# Array.net
KiCad netlist of a schematic drawn in Altium Designer
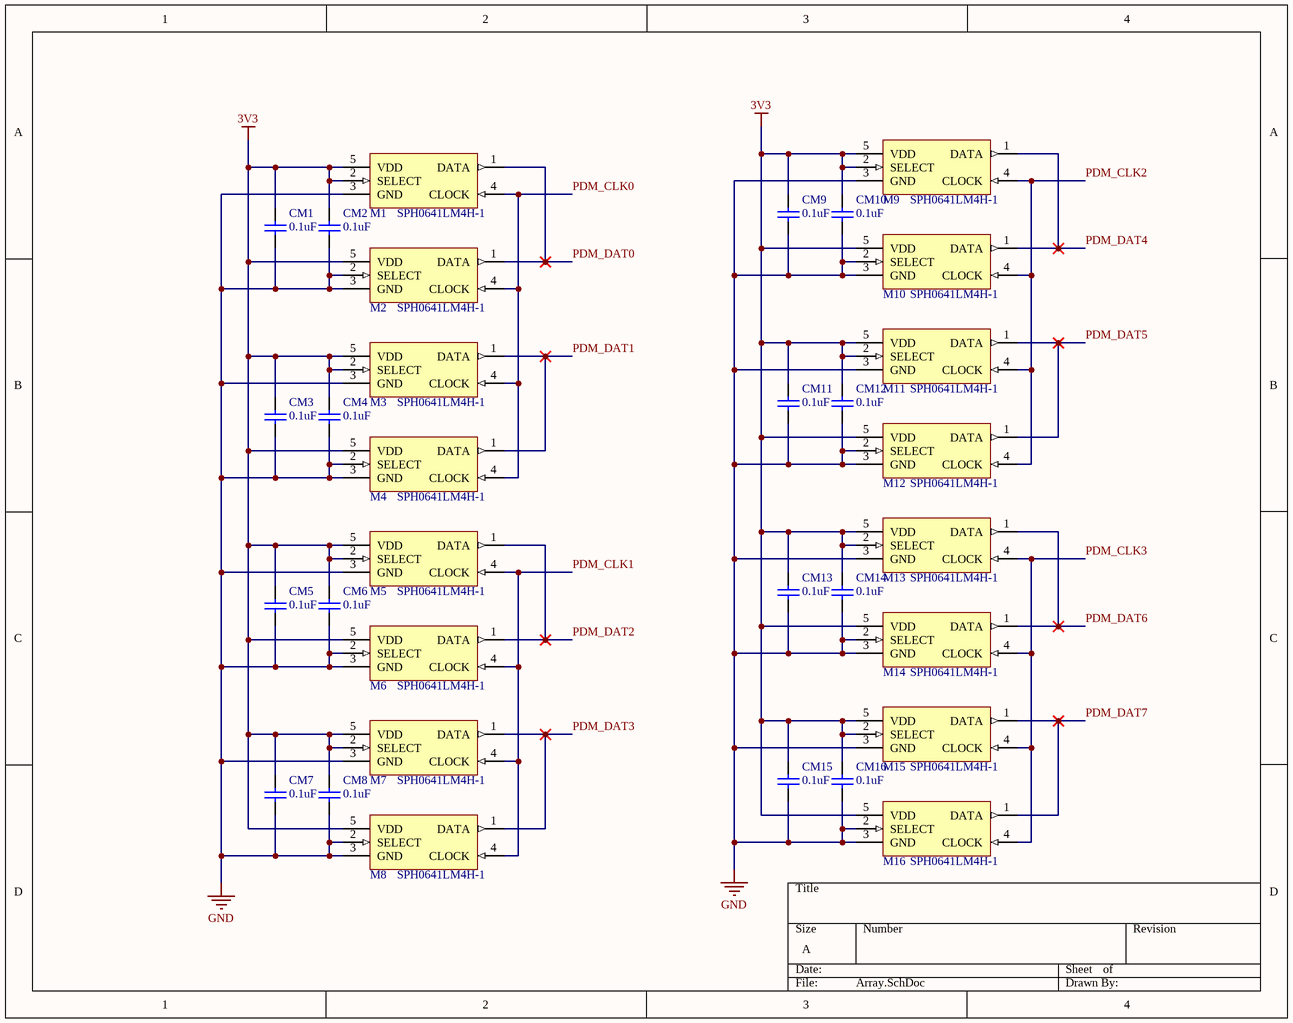
[diagram p0: Array.SchDoc]

(export (version "E")
  (design (tool "Eeschema 10.0.6"))
  (components
    (comp (ref "CM1")
      (value "0.1uF")
      (footprint "CHIP-0603")
      (description "Capacitor")
      (fields (field (name "PUBLISHER") "Altium Limited"))
      (libsource (lib "Miscellaneous Devices") (part "Cap"))
    )
    (comp (ref "CM2")
      (value "0.1uF")
      (footprint "CHIP-0603")
      (description "Capacitor")
      (fields (field (name "PUBLISHER") "Altium Limited"))
      (libsource (lib "Miscellaneous Devices") (part "Cap"))
    )
    (comp (ref "CM3")
      (value "0.1uF")
      (footprint "CHIP-0603")
      (description "Capacitor")
      (fields (field (name "PUBLISHER") "Altium Limited"))
      (libsource (lib "Miscellaneous Devices") (part "Cap"))
    )
    (comp (ref "CM4")
      (value "0.1uF")
      (footprint "CHIP-0603")
      (description "Capacitor")
      (fields (field (name "PUBLISHER") "Altium Limited"))
      (libsource (lib "Miscellaneous Devices") (part "Cap"))
    )
    (comp (ref "CM5")
      (value "0.1uF")
      (footprint "CHIP-0603")
      (description "Capacitor")
      (fields (field (name "PUBLISHER") "Altium Limited"))
      (libsource (lib "Miscellaneous Devices") (part "Cap"))
    )
    (comp (ref "CM6")
      (value "0.1uF")
      (footprint "CHIP-0603")
      (description "Capacitor")
      (fields (field (name "PUBLISHER") "Altium Limited"))
      (libsource (lib "Miscellaneous Devices") (part "Cap"))
    )
    (comp (ref "CM7")
      (value "0.1uF")
      (footprint "CHIP-0603")
      (description "Capacitor")
      (fields (field (name "PUBLISHER") "Altium Limited"))
      (libsource (lib "Miscellaneous Devices") (part "Cap"))
    )
    (comp (ref "CM8")
      (value "0.1uF")
      (footprint "CHIP-0603")
      (description "Capacitor")
      (fields (field (name "PUBLISHER") "Altium Limited"))
      (libsource (lib "Miscellaneous Devices") (part "Cap"))
    )
    (comp (ref "CM9")
      (value "0.1uF")
      (footprint "CHIP-0603")
      (description "Capacitor")
      (fields (field (name "PUBLISHER") "Altium Limited"))
      (libsource (lib "Miscellaneous Devices") (part "Cap"))
    )
    (comp (ref "CM10")
      (value "0.1uF")
      (footprint "CHIP-0603")
      (description "Capacitor")
      (fields (field (name "PUBLISHER") "Altium Limited"))
      (libsource (lib "Miscellaneous Devices") (part "Cap"))
    )
    (comp (ref "CM11")
      (value "0.1uF")
      (footprint "CHIP-0603")
      (description "Capacitor")
      (fields (field (name "PUBLISHER") "Altium Limited"))
      (libsource (lib "Miscellaneous Devices") (part "Cap"))
    )
    (comp (ref "CM12")
      (value "0.1uF")
      (footprint "CHIP-0603")
      (description "Capacitor")
      (fields (field (name "PUBLISHER") "Altium Limited"))
      (libsource (lib "Miscellaneous Devices") (part "Cap"))
    )
    (comp (ref "CM13")
      (value "0.1uF")
      (footprint "CHIP-0603")
      (description "Capacitor")
      (fields (field (name "PUBLISHER") "Altium Limited"))
      (libsource (lib "Miscellaneous Devices") (part "Cap"))
    )
    (comp (ref "CM14")
      (value "0.1uF")
      (footprint "CHIP-0603")
      (description "Capacitor")
      (fields (field (name "PUBLISHER") "Altium Limited"))
      (libsource (lib "Miscellaneous Devices") (part "Cap"))
    )
    (comp (ref "CM15")
      (value "0.1uF")
      (footprint "CHIP-0603")
      (description "Capacitor")
      (fields (field (name "PUBLISHER") "Altium Limited"))
      (libsource (lib "Miscellaneous Devices") (part "Cap"))
    )
    (comp (ref "CM16")
      (value "0.1uF")
      (footprint "CHIP-0603")
      (description "Capacitor")
      (fields (field (name "PUBLISHER") "Altium Limited"))
      (libsource (lib "Miscellaneous Devices") (part "Cap"))
    )
    (comp (ref "M1")
      (value "SPH0641LM4H-1")
      (footprint "SPH0641LM4H-1_KNO")
      (description "No Description Available")
      (fields (field (name "COPYRIGHT") "Copyright (C) 2023 Ultra Librarian. All rights reserved."))
      (libsource (lib "SPH0641LM4H-1") (part "SPH0641LM4H-1"))
    )
    (comp (ref "M2")
      (value "SPH0641LM4H-1")
      (footprint "SPH0641LM4H-1_KNO")
      (description "No Description Available")
      (fields (field (name "COPYRIGHT") "Copyright (C) 2023 Ultra Librarian. All rights reserved."))
      (libsource (lib "SPH0641LM4H-1") (part "SPH0641LM4H-1"))
    )
    (comp (ref "M3")
      (value "SPH0641LM4H-1")
      (footprint "SPH0641LM4H-1_KNO")
      (description "No Description Available")
      (fields (field (name "COPYRIGHT") "Copyright (C) 2023 Ultra Librarian. All rights reserved."))
      (libsource (lib "SPH0641LM4H-1") (part "SPH0641LM4H-1"))
    )
    (comp (ref "M4")
      (value "SPH0641LM4H-1")
      (footprint "SPH0641LM4H-1_KNO")
      (description "No Description Available")
      (fields (field (name "COPYRIGHT") "Copyright (C) 2023 Ultra Librarian. All rights reserved."))
      (libsource (lib "SPH0641LM4H-1") (part "SPH0641LM4H-1"))
    )
    (comp (ref "M5")
      (value "SPH0641LM4H-1")
      (footprint "SPH0641LM4H-1_KNO")
      (description "No Description Available")
      (fields (field (name "COPYRIGHT") "Copyright (C) 2023 Ultra Librarian. All rights reserved."))
      (libsource (lib "SPH0641LM4H-1") (part "SPH0641LM4H-1"))
    )
    (comp (ref "M6")
      (value "SPH0641LM4H-1")
      (footprint "SPH0641LM4H-1_KNO")
      (description "No Description Available")
      (fields (field (name "COPYRIGHT") "Copyright (C) 2023 Ultra Librarian. All rights reserved."))
      (libsource (lib "SPH0641LM4H-1") (part "SPH0641LM4H-1"))
    )
    (comp (ref "M7")
      (value "SPH0641LM4H-1")
      (footprint "SPH0641LM4H-1_KNO")
      (description "No Description Available")
      (fields (field (name "COPYRIGHT") "Copyright (C) 2023 Ultra Librarian. All rights reserved."))
      (libsource (lib "SPH0641LM4H-1") (part "SPH0641LM4H-1"))
    )
    (comp (ref "M8")
      (value "SPH0641LM4H-1")
      (footprint "SPH0641LM4H-1_KNO")
      (description "No Description Available")
      (fields (field (name "COPYRIGHT") "Copyright (C) 2023 Ultra Librarian. All rights reserved."))
      (libsource (lib "SPH0641LM4H-1") (part "SPH0641LM4H-1"))
    )
    (comp (ref "M9")
      (value "SPH0641LM4H-1")
      (footprint "SPH0641LM4H-1_KNO")
      (description "No Description Available")
      (fields (field (name "COPYRIGHT") "Copyright (C) 2023 Ultra Librarian. All rights reserved."))
      (libsource (lib "SPH0641LM4H-1") (part "SPH0641LM4H-1"))
    )
    (comp (ref "M10")
      (value "SPH0641LM4H-1")
      (footprint "SPH0641LM4H-1_KNO")
      (description "No Description Available")
      (fields (field (name "COPYRIGHT") "Copyright (C) 2023 Ultra Librarian. All rights reserved."))
      (libsource (lib "SPH0641LM4H-1") (part "SPH0641LM4H-1"))
    )
    (comp (ref "M11")
      (value "SPH0641LM4H-1")
      (footprint "SPH0641LM4H-1_KNO")
      (description "No Description Available")
      (fields (field (name "COPYRIGHT") "Copyright (C) 2023 Ultra Librarian. All rights reserved."))
      (libsource (lib "SPH0641LM4H-1") (part "SPH0641LM4H-1"))
    )
    (comp (ref "M12")
      (value "SPH0641LM4H-1")
      (footprint "SPH0641LM4H-1_KNO")
      (description "No Description Available")
      (fields (field (name "COPYRIGHT") "Copyright (C) 2023 Ultra Librarian. All rights reserved."))
      (libsource (lib "SPH0641LM4H-1") (part "SPH0641LM4H-1"))
    )
    (comp (ref "M13")
      (value "SPH0641LM4H-1")
      (footprint "SPH0641LM4H-1_KNO")
      (description "No Description Available")
      (fields (field (name "COPYRIGHT") "Copyright (C) 2023 Ultra Librarian. All rights reserved."))
      (libsource (lib "SPH0641LM4H-1") (part "SPH0641LM4H-1"))
    )
    (comp (ref "M14")
      (value "SPH0641LM4H-1")
      (footprint "SPH0641LM4H-1_KNO")
      (description "No Description Available")
      (fields (field (name "COPYRIGHT") "Copyright (C) 2023 Ultra Librarian. All rights reserved."))
      (libsource (lib "SPH0641LM4H-1") (part "SPH0641LM4H-1"))
    )
    (comp (ref "M15")
      (value "SPH0641LM4H-1")
      (footprint "SPH0641LM4H-1_KNO")
      (description "No Description Available")
      (fields (field (name "COPYRIGHT") "Copyright (C) 2023 Ultra Librarian. All rights reserved."))
      (libsource (lib "SPH0641LM4H-1") (part "SPH0641LM4H-1"))
    )
    (comp (ref "M16")
      (value "SPH0641LM4H-1")
      (footprint "SPH0641LM4H-1_KNO")
      (description "No Description Available")
      (fields (field (name "COPYRIGHT") "Copyright (C) 2023 Ultra Librarian. All rights reserved."))
      (libsource (lib "SPH0641LM4H-1") (part "SPH0641LM4H-1"))
    )
  )
  (nets
    (net (code "1") (name "/PDM_CLK0") (class "Default")
      (node (ref "M1") (pin "4") (pinfunction "CLOCK_4") (pintype "input"))
      (node (ref "M2") (pin "4") (pinfunction "CLOCK_4") (pintype "input"))
      (node (ref "M3") (pin "4") (pinfunction "CLOCK_4") (pintype "input"))
      (node (ref "M4") (pin "4") (pinfunction "CLOCK_4") (pintype "input"))
    )
    (net (code "2") (name "/PDM_CLK1") (class "Default")
      (node (ref "M5") (pin "4") (pinfunction "CLOCK_4") (pintype "input"))
      (node (ref "M6") (pin "4") (pinfunction "CLOCK_4") (pintype "input"))
      (node (ref "M7") (pin "4") (pinfunction "CLOCK_4") (pintype "input"))
      (node (ref "M8") (pin "4") (pinfunction "CLOCK_4") (pintype "input"))
    )
    (net (code "3") (name "/PDM_CLK2") (class "Default")
      (node (ref "M10") (pin "4") (pinfunction "CLOCK_4") (pintype "input"))
      (node (ref "M11") (pin "4") (pinfunction "CLOCK_4") (pintype "input"))
      (node (ref "M12") (pin "4") (pinfunction "CLOCK_4") (pintype "input"))
      (node (ref "M9") (pin "4") (pinfunction "CLOCK_4") (pintype "input"))
    )
    (net (code "4") (name "/PDM_CLK3") (class "Default")
      (node (ref "M13") (pin "4") (pinfunction "CLOCK_4") (pintype "input"))
      (node (ref "M14") (pin "4") (pinfunction "CLOCK_4") (pintype "input"))
      (node (ref "M15") (pin "4") (pinfunction "CLOCK_4") (pintype "input"))
      (node (ref "M16") (pin "4") (pinfunction "CLOCK_4") (pintype "input"))
    )
    (net (code "5") (name "/PDM_DAT0") (class "Default")
      (node (ref "M1") (pin "1") (pinfunction "DATA_1") (pintype "output"))
      (node (ref "M2") (pin "1") (pinfunction "DATA_1") (pintype "output"))
    )
    (net (code "6") (name "/PDM_DAT1") (class "Default")
      (node (ref "M3") (pin "1") (pinfunction "DATA_1") (pintype "output"))
      (node (ref "M4") (pin "1") (pinfunction "DATA_1") (pintype "output"))
    )
    (net (code "7") (name "/PDM_DAT2") (class "Default")
      (node (ref "M5") (pin "1") (pinfunction "DATA_1") (pintype "output"))
      (node (ref "M6") (pin "1") (pinfunction "DATA_1") (pintype "output"))
    )
    (net (code "8") (name "/PDM_DAT3") (class "Default")
      (node (ref "M7") (pin "1") (pinfunction "DATA_1") (pintype "output"))
      (node (ref "M8") (pin "1") (pinfunction "DATA_1") (pintype "output"))
    )
    (net (code "9") (name "/PDM_DAT4") (class "Default")
      (node (ref "M10") (pin "1") (pinfunction "DATA_1") (pintype "output"))
      (node (ref "M9") (pin "1") (pinfunction "DATA_1") (pintype "output"))
    )
    (net (code "10") (name "/PDM_DAT5") (class "Default")
      (node (ref "M11") (pin "1") (pinfunction "DATA_1") (pintype "output"))
      (node (ref "M12") (pin "1") (pinfunction "DATA_1") (pintype "output"))
    )
    (net (code "11") (name "/PDM_DAT6") (class "Default")
      (node (ref "M13") (pin "1") (pinfunction "DATA_1") (pintype "output"))
      (node (ref "M14") (pin "1") (pinfunction "DATA_1") (pintype "output"))
    )
    (net (code "12") (name "/PDM_DAT7") (class "Default")
      (node (ref "M15") (pin "1") (pinfunction "DATA_1") (pintype "output"))
      (node (ref "M16") (pin "1") (pinfunction "DATA_1") (pintype "output"))
    )
    (net (code "13") (name "3V3") (class "Default")
      (node (ref "CM1") (pin "2") (pinfunction "2_2") (pintype "passive"))
      (node (ref "CM10") (pin "2") (pinfunction "2_2") (pintype "passive"))
      (node (ref "CM11") (pin "2") (pinfunction "2_2") (pintype "passive"))
      (node (ref "CM12") (pin "2") (pinfunction "2_2") (pintype "passive"))
      (node (ref "CM13") (pin "2") (pinfunction "2_2") (pintype "passive"))
      (node (ref "CM14") (pin "2") (pinfunction "2_2") (pintype "passive"))
      (node (ref "CM15") (pin "2") (pinfunction "2_2") (pintype "passive"))
      (node (ref "CM16") (pin "2") (pinfunction "2_2") (pintype "passive"))
      (node (ref "CM2") (pin "2") (pinfunction "2_2") (pintype "passive"))
      (node (ref "CM3") (pin "2") (pinfunction "2_2") (pintype "passive"))
      (node (ref "CM4") (pin "2") (pinfunction "2_2") (pintype "passive"))
      (node (ref "CM5") (pin "2") (pinfunction "2_2") (pintype "passive"))
      (node (ref "CM6") (pin "2") (pinfunction "2_2") (pintype "passive"))
      (node (ref "CM7") (pin "2") (pinfunction "2_2") (pintype "passive"))
      (node (ref "CM8") (pin "2") (pinfunction "2_2") (pintype "passive"))
      (node (ref "CM9") (pin "2") (pinfunction "2_2") (pintype "passive"))
      (node (ref "M1") (pin "2") (pinfunction "SELECT_2") (pintype "input"))
      (node (ref "M1") (pin "5") (pinfunction "VDD_5") (pintype "power_in"))
      (node (ref "M10") (pin "5") (pinfunction "VDD_5") (pintype "power_in"))
      (node (ref "M11") (pin "2") (pinfunction "SELECT_2") (pintype "input"))
      (node (ref "M11") (pin "5") (pinfunction "VDD_5") (pintype "power_in"))
      (node (ref "M12") (pin "5") (pinfunction "VDD_5") (pintype "power_in"))
      (node (ref "M13") (pin "2") (pinfunction "SELECT_2") (pintype "input"))
      (node (ref "M13") (pin "5") (pinfunction "VDD_5") (pintype "power_in"))
      (node (ref "M14") (pin "5") (pinfunction "VDD_5") (pintype "power_in"))
      (node (ref "M15") (pin "2") (pinfunction "SELECT_2") (pintype "input"))
      (node (ref "M15") (pin "5") (pinfunction "VDD_5") (pintype "power_in"))
      (node (ref "M16") (pin "5") (pinfunction "VDD_5") (pintype "power_in"))
      (node (ref "M2") (pin "5") (pinfunction "VDD_5") (pintype "power_in"))
      (node (ref "M3") (pin "2") (pinfunction "SELECT_2") (pintype "input"))
      (node (ref "M3") (pin "5") (pinfunction "VDD_5") (pintype "power_in"))
      (node (ref "M4") (pin "5") (pinfunction "VDD_5") (pintype "power_in"))
      (node (ref "M5") (pin "2") (pinfunction "SELECT_2") (pintype "input"))
      (node (ref "M5") (pin "5") (pinfunction "VDD_5") (pintype "power_in"))
      (node (ref "M6") (pin "5") (pinfunction "VDD_5") (pintype "power_in"))
      (node (ref "M7") (pin "2") (pinfunction "SELECT_2") (pintype "input"))
      (node (ref "M7") (pin "5") (pinfunction "VDD_5") (pintype "power_in"))
      (node (ref "M8") (pin "5") (pinfunction "VDD_5") (pintype "power_in"))
      (node (ref "M9") (pin "2") (pinfunction "SELECT_2") (pintype "input"))
      (node (ref "M9") (pin "5") (pinfunction "VDD_5") (pintype "power_in"))
    )
    (net (code "14") (name "GND") (class "Default")
      (node (ref "CM1") (pin "1") (pinfunction "1_1") (pintype "passive"))
      (node (ref "CM10") (pin "1") (pinfunction "1_1") (pintype "passive"))
      (node (ref "CM11") (pin "1") (pinfunction "1_1") (pintype "passive"))
      (node (ref "CM12") (pin "1") (pinfunction "1_1") (pintype "passive"))
      (node (ref "CM13") (pin "1") (pinfunction "1_1") (pintype "passive"))
      (node (ref "CM14") (pin "1") (pinfunction "1_1") (pintype "passive"))
      (node (ref "CM15") (pin "1") (pinfunction "1_1") (pintype "passive"))
      (node (ref "CM16") (pin "1") (pinfunction "1_1") (pintype "passive"))
      (node (ref "CM2") (pin "1") (pinfunction "1_1") (pintype "passive"))
      (node (ref "CM3") (pin "1") (pinfunction "1_1") (pintype "passive"))
      (node (ref "CM4") (pin "1") (pinfunction "1_1") (pintype "passive"))
      (node (ref "CM5") (pin "1") (pinfunction "1_1") (pintype "passive"))
      (node (ref "CM6") (pin "1") (pinfunction "1_1") (pintype "passive"))
      (node (ref "CM7") (pin "1") (pinfunction "1_1") (pintype "passive"))
      (node (ref "CM8") (pin "1") (pinfunction "1_1") (pintype "passive"))
      (node (ref "CM9") (pin "1") (pinfunction "1_1") (pintype "passive"))
      (node (ref "M1") (pin "3") (pinfunction "GND_3") (pintype "passive"))
      (node (ref "M10") (pin "2") (pinfunction "SELECT_2") (pintype "input"))
      (node (ref "M10") (pin "3") (pinfunction "GND_3") (pintype "passive"))
      (node (ref "M11") (pin "3") (pinfunction "GND_3") (pintype "passive"))
      (node (ref "M12") (pin "2") (pinfunction "SELECT_2") (pintype "input"))
      (node (ref "M12") (pin "3") (pinfunction "GND_3") (pintype "passive"))
      (node (ref "M13") (pin "3") (pinfunction "GND_3") (pintype "passive"))
      (node (ref "M14") (pin "2") (pinfunction "SELECT_2") (pintype "input"))
      (node (ref "M14") (pin "3") (pinfunction "GND_3") (pintype "passive"))
      (node (ref "M15") (pin "3") (pinfunction "GND_3") (pintype "passive"))
      (node (ref "M16") (pin "2") (pinfunction "SELECT_2") (pintype "input"))
      (node (ref "M16") (pin "3") (pinfunction "GND_3") (pintype "passive"))
      (node (ref "M2") (pin "2") (pinfunction "SELECT_2") (pintype "input"))
      (node (ref "M2") (pin "3") (pinfunction "GND_3") (pintype "passive"))
      (node (ref "M3") (pin "3") (pinfunction "GND_3") (pintype "passive"))
      (node (ref "M4") (pin "2") (pinfunction "SELECT_2") (pintype "input"))
      (node (ref "M4") (pin "3") (pinfunction "GND_3") (pintype "passive"))
      (node (ref "M5") (pin "3") (pinfunction "GND_3") (pintype "passive"))
      (node (ref "M6") (pin "2") (pinfunction "SELECT_2") (pintype "input"))
      (node (ref "M6") (pin "3") (pinfunction "GND_3") (pintype "passive"))
      (node (ref "M7") (pin "3") (pinfunction "GND_3") (pintype "passive"))
      (node (ref "M8") (pin "2") (pinfunction "SELECT_2") (pintype "input"))
      (node (ref "M8") (pin "3") (pinfunction "GND_3") (pintype "passive"))
      (node (ref "M9") (pin "3") (pinfunction "GND_3") (pintype "passive"))
    )
  )
)
